# 3V3_to_0V9.net
KiCad netlist of a schematic drawn in Altium Designer
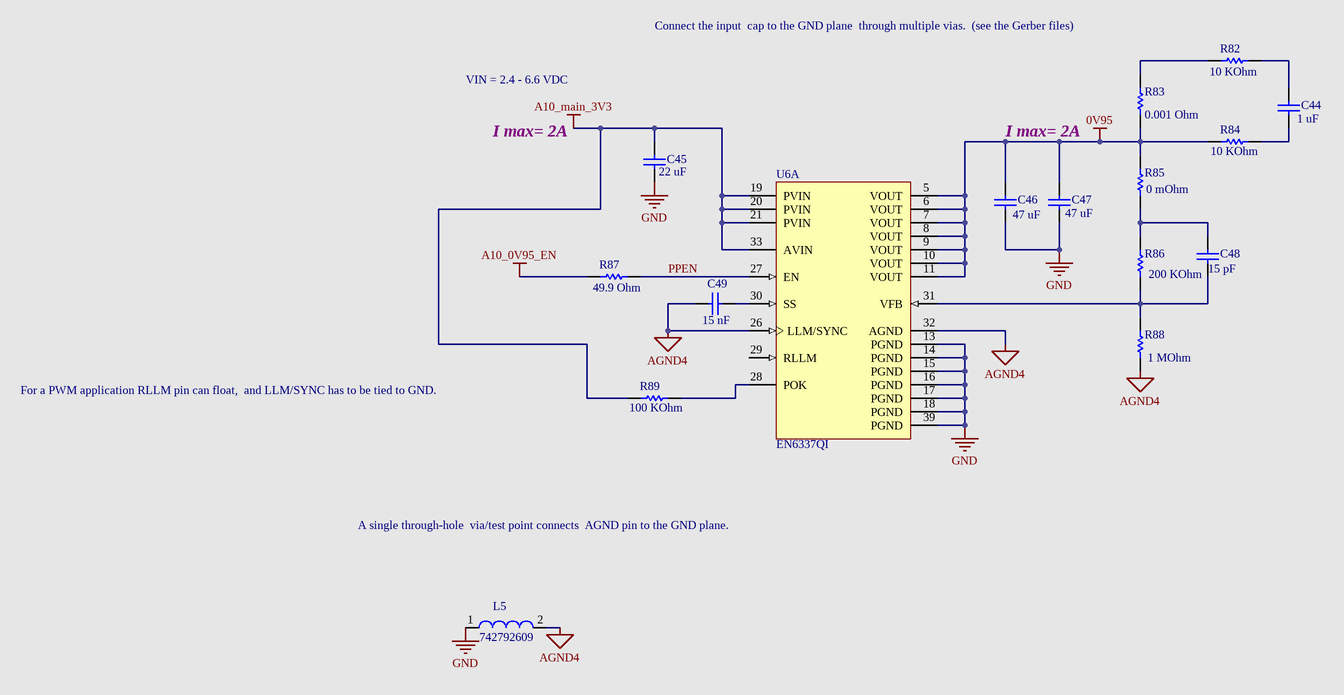
[diagram p0: 3V3_to_0V9.SchDoc]

(export (version "E")
  (design (tool "Eeschema 10.0.6"))
  (components
    (comp (ref "C44")
      (value "CGB2A1X5R1E105K033BC")
      (footprint "CAPC1005X33X10LL5")
      (description "Chip Capacitor, 1 uF, +/- 10%, 25 V, -55 to 85 degC, 0402 (1005 Metric), RoHS, Tape and Reel")
      (fields (field (name "TOLERANCE") "10%") (field (name "CAPACITANCE") "1 uF"))
      (libsource (lib "Altium Content Vault") (part "CAP-NP-2"))
    )
    (comp (ref "C45")
      (value "GRM31CR61E226KE15L")
      (footprint "CAPC3216X180X55ML20T25")
      (description "Chip Capacitor, 22 uF, +/- 10%, 25 V, -55 to 85 degC, 1206 (3216 Metric), RoHS, Tape and Reel")
      (fields (field (name "TOLERANCE") "10%") (field (name "CAPACITANCE") "22 uF"))
      (libsource (lib "") (part "CAP-NP-2_1"))
    )
    (comp (ref "C46")
      (value "C3216X5R1A476M160AB")
      (footprint "CAPC3216X180X20ML20")
      (description "Chip Capacitor, 47 uF, +/- 20%, 10 V, -55 to 85 degC, 1206 (3216 Metric), RoHS, Tape and Reel")
      (fields (field (name "TOLERANCE") "20%") (field (name "CAPACITANCE") "47 uF"))
      (libsource (lib "Altium Content Vault") (part "CAP-NP-2"))
    )
    (comp (ref "C47")
      (value "C3216X5R1A476M160AB")
      (footprint "CAPC3216X180X20ML20")
      (description "Chip Capacitor, 47 uF, +/- 20%, 10 V, -55 to 85 degC, 1206 (3216 Metric), RoHS, Tape and Reel")
      (fields (field (name "TOLERANCE") "20%") (field (name "CAPACITANCE") "47 uF"))
      (libsource (lib "Altium Content Vault") (part "CAP-NP-2"))
    )
    (comp (ref "C48")
      (value "ECJ-0EC1H150J")
      (footprint "CAPC1005X55X20ML5T10")
      (description "Chip Capacitor,15 pF, +/- 5%, 50 V, -55 to 125 degC, 0402 (1005 Metric), RoHS, Tape and Reel")
      (fields (field (name "TOLERANCE") "5%") (field (name "CAPACITANCE") "15 pF"))
      (libsource (lib "Altium Content Vault") (part "CAP-NP-2"))
    )
    (comp (ref "C49")
      (value "VJ0402Y153JXQPW1BC")
      (footprint "CAPC1005X55X23ML05T8")
      (description "Chip Capacitor, 15 nF, +/- 5%, 10 V, -55 to 125 degC, 0402 (1005 Metric), RoHS, Tape and Reel")
      (fields (field (name "CAPACITANCE") "15 nF") (field (name "TOLERANCE") "5%"))
      (libsource (lib "") (part "CAP-NP-2_1"))
    )
    (comp (ref "L5")
      (value "742792609")
      (footprint "SMD-0603")
      (description "SMD EMI Suppression Ferrite Bead WE-CBF, Z = 30 Ohm")
      (libsource (lib "Altium Content Vault") (part "CMP-0220-00193-1"))
    )
    (comp (ref "R82")
      (value "ERJ-2RKF1002X")
      (footprint "RESC1005X40X25NL05T05")
      (description "Chip Resistor, 10 KOhm, +/- 1%, 100 mW, -55 to 155 degC, 0402 (1005 Metric), RoHS, Tape and Reel")
      (fields
        (field (name "TOLERANCE") "1%")
        (field (name "RESISTANCE") "10 KOhm")
        (field (name "MANUFACTURER") "Basic Passives")
      )
      (libsource (lib "Altium Content Vault") (part "RES-2"))
    )
    (comp (ref "R83")
      (value "WSLP12061L000FEA")
      (footprint "RESC3216X89X104LL25T25")
      (description "Chip Resistor, 0.001 Ohm, +/- 1%, 1 W, -65 to 170 degC, 1206 (3216 Metric), RoHS, Tape and Reel")
      (fields (field (name "TOLERANCE") "1%") (field (name "RESISTANCE") "0.001 Ohm"))
      (libsource (lib "Altium Content Vault") (part "RES-2"))
    )
    (comp (ref "R84")
      (value "ERJ-2RKF1002X")
      (footprint "RESC1005X40X25NL05T05")
      (description "Chip Resistor, 10 KOhm, +/- 1%, 100 mW, -55 to 155 degC, 0402 (1005 Metric), RoHS, Tape and Reel")
      (fields
        (field (name "TOLERANCE") "1%")
        (field (name "RESISTANCE") "10 KOhm")
        (field (name "MANUFACTURER") "Basic Passives")
      )
      (libsource (lib "Altium Content Vault") (part "RES-2"))
    )
    (comp (ref "R85")
      (value "ERJ-2GE0R00X")
      (footprint "RESC1005X40X25ML05T05")
      (description "Chip Resistor, 0 mOhm, +/- 5%, 100 mW, -55 to 155 degC, 0402 (1005 Metric), RoHS, Tape and Reel")
      (fields
        (field (name "TOLERANCE") "5%")
        (field (name "RESISTANCE") "0 mOhm")
        (field (name "MANUFACTURER") "Basic Passives")
      )
      (libsource (lib "Altium Content Vault") (part "RES-2"))
    )
    (comp (ref "R86")
      (value "ERJ-2RKF2003X")
      (footprint "RESC1005X40X25NL05T05")
      (description "Chip Resistor, 200 KOhm, +/- 1%, 100 mW, -55 to 155 degC, 0402 (1005 Metric), RoHS, Tape and Reel")
      (fields
        (field (name "RESISTANCE") "200 KOhm")
        (field (name "TOLERANCE") "1%")
        (field (name "MANUFACTURER") "Basic Passives")
      )
      (libsource (lib "Altium Content Vault") (part "RES-2"))
    )
    (comp (ref "R87")
      (value "NRC04F49R9TRF")
      (footprint "RESC1005X35X25NL8T10")
      (description "Chip Resistor, 49.9 Ohm, +/- 1%, 0.06 W, -55 to 155 degC, 0402 (1005 Metric), RoHS, Tape and Reel")
      (fields (field (name "TOLERANCE") "1%") (field (name "RESISTANCE") "49.9 Ohm"))
      (libsource (lib "Altium Content Vault") (part "RES-2"))
    )
    (comp (ref "R88")
      (value "ERJ-2RKF1004X")
      (footprint "RESC1005X40X25LL05T05")
      (description "Chip Resistor, 1 MOhm, +/- 1%, 100 mW, -55 to 155 degC, 0402 (1005 Metric), RoHS, Tape and Reel")
      (fields
        (field (name "TOLERANCE") "1%")
        (field (name "RESISTANCE") "1 MOhm")
        (field (name "MANUFACTURER") "Basic Passives")
      )
      (libsource (lib "Altium Content Vault") (part "RES-2"))
    )
    (comp (ref "R89")
      (value "ERJ-2RKF1003X")
      (footprint "RESC1005X40X25LL05T05")
      (description "Chip Resistor, 100 KOhm, +/- 1%, 100 mW, -55 to 155 degC, 0402 (1005 Metric), RoHS, Tape and Reel")
      (fields
        (field (name "RESISTANCE") "100 KOhm")
        (field (name "TOLERANCE") "1%")
        (field (name "MANUFACTURER") "Basic Passives")
      )
      (libsource (lib "Altium Content Vault") (part "RES-2"))
    )
    (comp (ref "U6")
      (value "EN6337QI")
      (footprint "ALTR-QFN-38_A-190_D1-193_V")
      (libsource (lib "Altium Content Vault") (part "ALTR-EN63X7QI-QFN38"))
    )
  )
  (nets
    (net (code "1") (name "/PPEN") (class "Default")
      (node (ref "R87") (pin "2") (pinfunction "2_2") (pintype "passive"))
      (node (ref "U6") (pin "27") (pinfunction "EN_27") (pintype "input"))
    )
    (net (code "2") (name "0V95") (class "Default")
      (node (ref "C46") (pin "2") (pinfunction "2_2") (pintype "passive"))
      (node (ref "C47") (pin "2") (pinfunction "2_2") (pintype "passive"))
      (node (ref "R83") (pin "2") (pinfunction "2_2") (pintype "passive"))
      (node (ref "R84") (pin "2") (pinfunction "2_2") (pintype "passive"))
      (node (ref "R85") (pin "1") (pinfunction "1_1") (pintype "passive"))
      (node (ref "U6") (pin "10") (pinfunction "VOUT_10") (pintype "power_in"))
      (node (ref "U6") (pin "11") (pinfunction "VOUT_11") (pintype "power_in"))
      (node (ref "U6") (pin "5") (pinfunction "VOUT_5") (pintype "power_in"))
      (node (ref "U6") (pin "6") (pinfunction "VOUT_6") (pintype "power_in"))
      (node (ref "U6") (pin "7") (pinfunction "VOUT_7") (pintype "power_in"))
      (node (ref "U6") (pin "8") (pinfunction "VOUT_8") (pintype "power_in"))
      (node (ref "U6") (pin "9") (pinfunction "VOUT_9") (pintype "power_in"))
    )
    (net (code "3") (name "A10_0V95_EN") (class "Default")
      (node (ref "R87") (pin "1") (pinfunction "1_1") (pintype "passive"))
    )
    (net (code "4") (name "A10_main_3V3") (class "Default")
      (node (ref "C45") (pin "2") (pinfunction "2_2") (pintype "passive"))
      (node (ref "R89") (pin "1") (pinfunction "1_1") (pintype "passive"))
      (node (ref "U6") (pin "19") (pinfunction "PVIN_19") (pintype "power_in"))
      (node (ref "U6") (pin "20") (pinfunction "PVIN_20") (pintype "power_in"))
      (node (ref "U6") (pin "21") (pinfunction "PVIN_21") (pintype "power_in"))
      (node (ref "U6") (pin "33") (pinfunction "AVIN_33") (pintype "power_in"))
    )
    (net (code "5") (name "AGND4") (class "Default")
      (node (ref "C49") (pin "1") (pinfunction "1_1") (pintype "passive"))
      (node (ref "L5") (pin "2") (pinfunction "2_2") (pintype "passive"))
      (node (ref "R88") (pin "1") (pinfunction "1_1") (pintype "passive"))
      (node (ref "U6") (pin "26") (pinfunction "LLM/SYNC_26") (pintype "input"))
      (node (ref "U6") (pin "32") (pinfunction "AGND_32") (pintype "power_in"))
    )
    (net (code "6") (name "GND") (class "Default")
      (node (ref "C45") (pin "1") (pinfunction "1_1") (pintype "passive"))
      (node (ref "C46") (pin "1") (pinfunction "1_1") (pintype "passive"))
      (node (ref "C47") (pin "1") (pinfunction "1_1") (pintype "passive"))
      (node (ref "L5") (pin "1") (pinfunction "1_1") (pintype "passive"))
      (node (ref "U6") (pin "13") (pinfunction "PGND_13") (pintype "power_in"))
      (node (ref "U6") (pin "14") (pinfunction "PGND_14") (pintype "power_in"))
      (node (ref "U6") (pin "15") (pinfunction "PGND_15") (pintype "power_in"))
      (node (ref "U6") (pin "16") (pinfunction "PGND_16") (pintype "power_in"))
      (node (ref "U6") (pin "17") (pinfunction "PGND_17") (pintype "power_in"))
      (node (ref "U6") (pin "18") (pinfunction "PGND_18") (pintype "power_in"))
      (node (ref "U6") (pin "39") (pinfunction "PGND_39") (pintype "power_in"))
    )
    (net (code "7") (name "Net-(C44-Pad1)") (class "Default")
      (node (ref "C44") (pin "1") (pinfunction "1_1") (pintype "passive"))
      (node (ref "R84") (pin "1") (pinfunction "1_1") (pintype "passive"))
    )
    (net (code "8") (name "Net-(C44-Pad2)") (class "Default")
      (node (ref "C44") (pin "2") (pinfunction "2_2") (pintype "passive"))
      (node (ref "R82") (pin "1") (pinfunction "1_1") (pintype "passive"))
    )
    (net (code "9") (name "Net-(C48-Pad2)") (class "Default")
      (node (ref "C48") (pin "2") (pinfunction "2_2") (pintype "passive"))
      (node (ref "R85") (pin "2") (pinfunction "2_2") (pintype "passive"))
      (node (ref "R86") (pin "2") (pinfunction "2_2") (pintype "passive"))
    )
    (net (code "10") (name "Net-(R82-Pad2)") (class "Default")
      (node (ref "R82") (pin "2") (pinfunction "2_2") (pintype "passive"))
      (node (ref "R83") (pin "1") (pinfunction "1_1") (pintype "passive"))
    )
    (net (code "11") (name "Net-(U6A-POK)") (class "Default")
      (node (ref "R89") (pin "2") (pinfunction "2_2") (pintype "passive"))
      (node (ref "U6") (pin "28") (pinfunction "POK_28") (pintype "open_collector"))
    )
    (net (code "12") (name "Net-(U6A-SS)") (class "Default")
      (node (ref "C49") (pin "2") (pinfunction "2_2") (pintype "passive"))
      (node (ref "U6") (pin "30") (pinfunction "SS_30") (pintype "input"))
    )
    (net (code "13") (name "Net-(U6A-VFB)") (class "Default")
      (node (ref "C48") (pin "1") (pinfunction "1_1") (pintype "passive"))
      (node (ref "R86") (pin "1") (pinfunction "1_1") (pintype "passive"))
      (node (ref "R88") (pin "2") (pinfunction "2_2") (pintype "passive"))
      (node (ref "U6") (pin "31") (pinfunction "VFB_31") (pintype "input"))
    )
    (net (code "14") (name "unconnected-(U6A-RLLM-Pad29)") (class "Default")
      (node (ref "U6") (pin "29") (pinfunction "RLLM_29") (pintype "input"))
    )
  )
)
